# pyro18_io.net
KiCad netlist of a schematic drawn in EAGLE
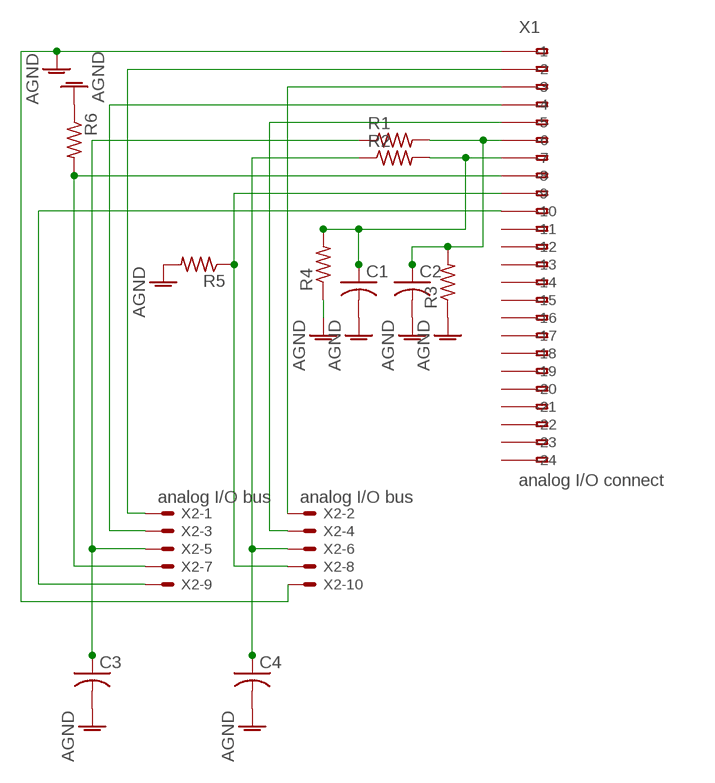
[diagram p0: schematic, sheet 1]

(export (version "E")
  (design (tool "Eeschema 10.0.6"))
  (components
    (comp (ref "C1")
      (value "C-US025-024X044")
      (footprint "eagle-import:C025-024X044")
      (libsource (lib "eagle-import") (part "C-US025-024X044"))
    )
    (comp (ref "C2")
      (value "C-US025-024X044")
      (footprint "eagle-import:C025-024X044")
      (libsource (lib "eagle-import") (part "C-US025-024X044"))
    )
    (comp (ref "C3")
      (value "C-US025-024X044")
      (footprint "eagle-import:C025-024X044")
      (libsource (lib "eagle-import") (part "C-US025-024X044"))
    )
    (comp (ref "C4")
      (value "C-US025-024X044")
      (footprint "eagle-import:C025-024X044")
      (libsource (lib "eagle-import") (part "C-US025-024X044"))
    )
    (comp (ref "R1")
      (value "R-US_0204/2V")
      (footprint "eagle-import:0204V")
      (libsource (lib "eagle-import") (part "R-US_0204/2V"))
    )
    (comp (ref "R2")
      (value "R-US_0204/2V")
      (footprint "eagle-import:0204V")
      (libsource (lib "eagle-import") (part "R-US_0204/2V"))
    )
    (comp (ref "R3")
      (value "R-US_0204/2V")
      (footprint "eagle-import:0204V")
      (libsource (lib "eagle-import") (part "R-US_0204/2V"))
    )
    (comp (ref "R4")
      (value "R-US_0204/2V")
      (footprint "eagle-import:0204V")
      (libsource (lib "eagle-import") (part "R-US_0204/2V"))
    )
    (comp (ref "R5")
      (value "R-US_0204/2V")
      (footprint "eagle-import:0204V")
      (libsource (lib "eagle-import") (part "R-US_0204/2V"))
    )
    (comp (ref "R6")
      (value "R-US_0204/2V")
      (footprint "eagle-import:0204V")
      (libsource (lib "eagle-import") (part "R-US_0204/2V"))
    )
    (comp (ref "X1")
      (value "analog I/O connect")
      (footprint "eagle-import:233-224")
      (fields (field (name "MPN") "233-224"))
      (libsource (lib "eagle-import") (part "233-224"))
    )
    (comp (ref "X2")
      (value "analog I/O bus")
      (footprint "eagle-import:332-10")
      (libsource (lib "eagle-import") (part "332-10"))
    )
  )
  (nets
    (net (code "1") (name "AGND") (class "Default")
      (node (ref "C1") (pin "2") (pinfunction "2_2") (pintype "passive"))
      (node (ref "C2") (pin "2") (pinfunction "2_2") (pintype "passive"))
      (node (ref "C3") (pin "2") (pinfunction "2_2") (pintype "passive"))
      (node (ref "C4") (pin "2") (pinfunction "2_2") (pintype "passive"))
      (node (ref "R3") (pin "1") (pinfunction "1_1") (pintype "passive"))
      (node (ref "R4") (pin "1") (pinfunction "1_1") (pintype "passive"))
      (node (ref "R5") (pin "2") (pinfunction "2_2") (pintype "passive"))
      (node (ref "R6") (pin "1") (pinfunction "1_1") (pintype "passive"))
      (node (ref "X1") (pin "A1") (pinfunction "-1_A1") (pintype "passive"))
      (node (ref "X2") (pin "10") (pinfunction "S_10") (pintype "passive"))
    )
    (net (code "2") (name "Net-(X1--2)") (class "Default")
      (node (ref "X1") (pin "A2") (pinfunction "-2_A2") (pintype "passive"))
      (node (ref "X2") (pin "1") (pinfunction "S_1") (pintype "passive"))
    )
    (net (code "3") (name "Net-(X1--3)") (class "Default")
      (node (ref "X1") (pin "A3") (pinfunction "-3_A3") (pintype "passive"))
      (node (ref "X2") (pin "2") (pinfunction "S_2") (pintype "passive"))
    )
    (net (code "4") (name "Net-(X1--4)") (class "Default")
      (node (ref "X1") (pin "A4") (pinfunction "-4_A4") (pintype "passive"))
      (node (ref "X2") (pin "3") (pinfunction "S_3") (pintype "passive"))
    )
    (net (code "5") (name "Net-(X1--5)") (class "Default")
      (node (ref "X1") (pin "A5") (pinfunction "-5_A5") (pintype "passive"))
      (node (ref "X2") (pin "4") (pinfunction "S_4") (pintype "passive"))
    )
    (net (code "6") (name "Net-(X1--6)") (class "Default")
      (node (ref "C2") (pin "1") (pinfunction "1_1") (pintype "passive"))
      (node (ref "R1") (pin "2") (pinfunction "2_2") (pintype "passive"))
      (node (ref "R3") (pin "2") (pinfunction "2_2") (pintype "passive"))
      (node (ref "X1") (pin "A6") (pinfunction "-6_A6") (pintype "passive"))
    )
    (net (code "7") (name "Net-(X1--7)") (class "Default")
      (node (ref "C1") (pin "1") (pinfunction "1_1") (pintype "passive"))
      (node (ref "R2") (pin "2") (pinfunction "2_2") (pintype "passive"))
      (node (ref "R4") (pin "2") (pinfunction "2_2") (pintype "passive"))
      (node (ref "X1") (pin "A7") (pinfunction "-7_A7") (pintype "passive"))
    )
    (net (code "8") (name "Net-(X1--8)") (class "Default")
      (node (ref "R6") (pin "2") (pinfunction "2_2") (pintype "passive"))
      (node (ref "X1") (pin "A8") (pinfunction "-8_A8") (pintype "passive"))
      (node (ref "X2") (pin "7") (pinfunction "S_7") (pintype "passive"))
    )
    (net (code "9") (name "Net-(X1--9)") (class "Default")
      (node (ref "R5") (pin "1") (pinfunction "1_1") (pintype "passive"))
      (node (ref "X1") (pin "A9") (pinfunction "-9_A9") (pintype "passive"))
      (node (ref "X2") (pin "8") (pinfunction "S_8") (pintype "passive"))
    )
    (net (code "10") (name "Net-(X1--10)") (class "Default")
      (node (ref "X1") (pin "A10") (pinfunction "-10_A10") (pintype "passive"))
      (node (ref "X2") (pin "9") (pinfunction "S_9") (pintype "passive"))
    )
    (net (code "11") (name "Net-(X2F-S)") (class "Default")
      (node (ref "C3") (pin "1") (pinfunction "1_1") (pintype "passive"))
      (node (ref "R1") (pin "1") (pinfunction "1_1") (pintype "passive"))
      (node (ref "X2") (pin "5") (pinfunction "S_5") (pintype "passive"))
    )
    (net (code "12") (name "Net-(X2G-S)") (class "Default")
      (node (ref "C4") (pin "1") (pinfunction "1_1") (pintype "passive"))
      (node (ref "R2") (pin "1") (pinfunction "1_1") (pintype "passive"))
      (node (ref "X2") (pin "6") (pinfunction "S_6") (pintype "passive"))
    )
    (net (code "13") (name "unconnected-(X1--11-PadA11)") (class "Default")
      (node (ref "X1") (pin "A11") (pinfunction "-11_A11") (pintype "passive"))
    )
    (net (code "14") (name "unconnected-(X1--12-PadA12)") (class "Default")
      (node (ref "X1") (pin "A12") (pinfunction "-12_A12") (pintype "passive"))
    )
    (net (code "15") (name "unconnected-(X1--13-PadA13)") (class "Default")
      (node (ref "X1") (pin "A13") (pinfunction "-13_A13") (pintype "passive"))
    )
    (net (code "16") (name "unconnected-(X1--14-PadA14)") (class "Default")
      (node (ref "X1") (pin "A14") (pinfunction "-14_A14") (pintype "passive"))
    )
    (net (code "17") (name "unconnected-(X1--15-PadA15)") (class "Default")
      (node (ref "X1") (pin "A15") (pinfunction "-15_A15") (pintype "passive"))
    )
    (net (code "18") (name "unconnected-(X1--16-PadA16)") (class "Default")
      (node (ref "X1") (pin "A16") (pinfunction "-16_A16") (pintype "passive"))
    )
    (net (code "19") (name "unconnected-(X1--17-PadA17)") (class "Default")
      (node (ref "X1") (pin "A17") (pinfunction "-17_A17") (pintype "passive"))
    )
    (net (code "20") (name "unconnected-(X1--18-PadA18)") (class "Default")
      (node (ref "X1") (pin "A18") (pinfunction "-18_A18") (pintype "passive"))
    )
    (net (code "21") (name "unconnected-(X1--19-PadA19)") (class "Default")
      (node (ref "X1") (pin "A19") (pinfunction "-19_A19") (pintype "passive"))
    )
    (net (code "22") (name "unconnected-(X1--20-PadA20)") (class "Default")
      (node (ref "X1") (pin "A20") (pinfunction "-20_A20") (pintype "passive"))
    )
    (net (code "23") (name "unconnected-(X1--21-PadA21)") (class "Default")
      (node (ref "X1") (pin "A21") (pinfunction "-21_A21") (pintype "passive"))
    )
    (net (code "24") (name "unconnected-(X1--22-PadA22)") (class "Default")
      (node (ref "X1") (pin "A22") (pinfunction "-22_A22") (pintype "passive"))
    )
    (net (code "25") (name "unconnected-(X1--23-PadA23)") (class "Default")
      (node (ref "X1") (pin "A23") (pinfunction "-23_A23") (pintype "passive"))
    )
    (net (code "26") (name "unconnected-(X1--24-PadA24)") (class "Default")
      (node (ref "X1") (pin "A24") (pinfunction "-24_A24") (pintype "passive"))
    )
    (net (code "27") (name "unconnected-(X1-B-1-PadB1)") (class "Default")
      (node (ref "X1") (pin "B1") (pinfunction "B-1_B1") (pintype "passive"))
    )
    (net (code "28") (name "unconnected-(X1-B-2-PadB2)") (class "Default")
      (node (ref "X1") (pin "B2") (pinfunction "B-2_B2") (pintype "passive"))
    )
    (net (code "29") (name "unconnected-(X1-B-3-PadB3)") (class "Default")
      (node (ref "X1") (pin "B3") (pinfunction "B-3_B3") (pintype "passive"))
    )
    (net (code "30") (name "unconnected-(X1-B-4-PadB4)") (class "Default")
      (node (ref "X1") (pin "B4") (pinfunction "B-4_B4") (pintype "passive"))
    )
    (net (code "31") (name "unconnected-(X1-B-5-PadB5)") (class "Default")
      (node (ref "X1") (pin "B5") (pinfunction "B-5_B5") (pintype "passive"))
    )
    (net (code "32") (name "unconnected-(X1-B-6-PadB6)") (class "Default")
      (node (ref "X1") (pin "B6") (pinfunction "B-6_B6") (pintype "passive"))
    )
    (net (code "33") (name "unconnected-(X1-B-7-PadB7)") (class "Default")
      (node (ref "X1") (pin "B7") (pinfunction "B-7_B7") (pintype "passive"))
    )
    (net (code "34") (name "unconnected-(X1-B-8-PadB8)") (class "Default")
      (node (ref "X1") (pin "B8") (pinfunction "B-8_B8") (pintype "passive"))
    )
    (net (code "35") (name "unconnected-(X1-B-9-PadB9)") (class "Default")
      (node (ref "X1") (pin "B9") (pinfunction "B-9_B9") (pintype "passive"))
    )
    (net (code "36") (name "unconnected-(X1-B-10-PadB10)") (class "Default")
      (node (ref "X1") (pin "B10") (pinfunction "B-10_B10") (pintype "passive"))
    )
    (net (code "37") (name "unconnected-(X1-B-11-PadB11)") (class "Default")
      (node (ref "X1") (pin "B11") (pinfunction "B-11_B11") (pintype "passive"))
    )
    (net (code "38") (name "unconnected-(X1-B-12-PadB12)") (class "Default")
      (node (ref "X1") (pin "B12") (pinfunction "B-12_B12") (pintype "passive"))
    )
    (net (code "39") (name "unconnected-(X1-B-13-PadB13)") (class "Default")
      (node (ref "X1") (pin "B13") (pinfunction "B-13_B13") (pintype "passive"))
    )
    (net (code "40") (name "unconnected-(X1-B-14-PadB14)") (class "Default")
      (node (ref "X1") (pin "B14") (pinfunction "B-14_B14") (pintype "passive"))
    )
    (net (code "41") (name "unconnected-(X1-B-15-PadB15)") (class "Default")
      (node (ref "X1") (pin "B15") (pinfunction "B-15_B15") (pintype "passive"))
    )
    (net (code "42") (name "unconnected-(X1-B-16-PadB16)") (class "Default")
      (node (ref "X1") (pin "B16") (pinfunction "B-16_B16") (pintype "passive"))
    )
    (net (code "43") (name "unconnected-(X1-B-17-PadB17)") (class "Default")
      (node (ref "X1") (pin "B17") (pinfunction "B-17_B17") (pintype "passive"))
    )
    (net (code "44") (name "unconnected-(X1-B-18-PadB18)") (class "Default")
      (node (ref "X1") (pin "B18") (pinfunction "B-18_B18") (pintype "passive"))
    )
    (net (code "45") (name "unconnected-(X1-B-19-PadB19)") (class "Default")
      (node (ref "X1") (pin "B19") (pinfunction "B-19_B19") (pintype "passive"))
    )
    (net (code "46") (name "unconnected-(X1-B-20-PadB20)") (class "Default")
      (node (ref "X1") (pin "B20") (pinfunction "B-20_B20") (pintype "passive"))
    )
    (net (code "47") (name "unconnected-(X1-B-21-PadB21)") (class "Default")
      (node (ref "X1") (pin "B21") (pinfunction "B-21_B21") (pintype "passive"))
    )
    (net (code "48") (name "unconnected-(X1-B-22-PadB22)") (class "Default")
      (node (ref "X1") (pin "B22") (pinfunction "B-22_B22") (pintype "passive"))
    )
    (net (code "49") (name "unconnected-(X1-B-23-PadB23)") (class "Default")
      (node (ref "X1") (pin "B23") (pinfunction "B-23_B23") (pintype "passive"))
    )
    (net (code "50") (name "unconnected-(X1-B-24-PadB24)") (class "Default")
      (node (ref "X1") (pin "B24") (pinfunction "B-24_B24") (pintype "passive"))
    )
  )
)
